# 05-USB-UART.net
KiCad netlist of a schematic drawn in Altium Designer
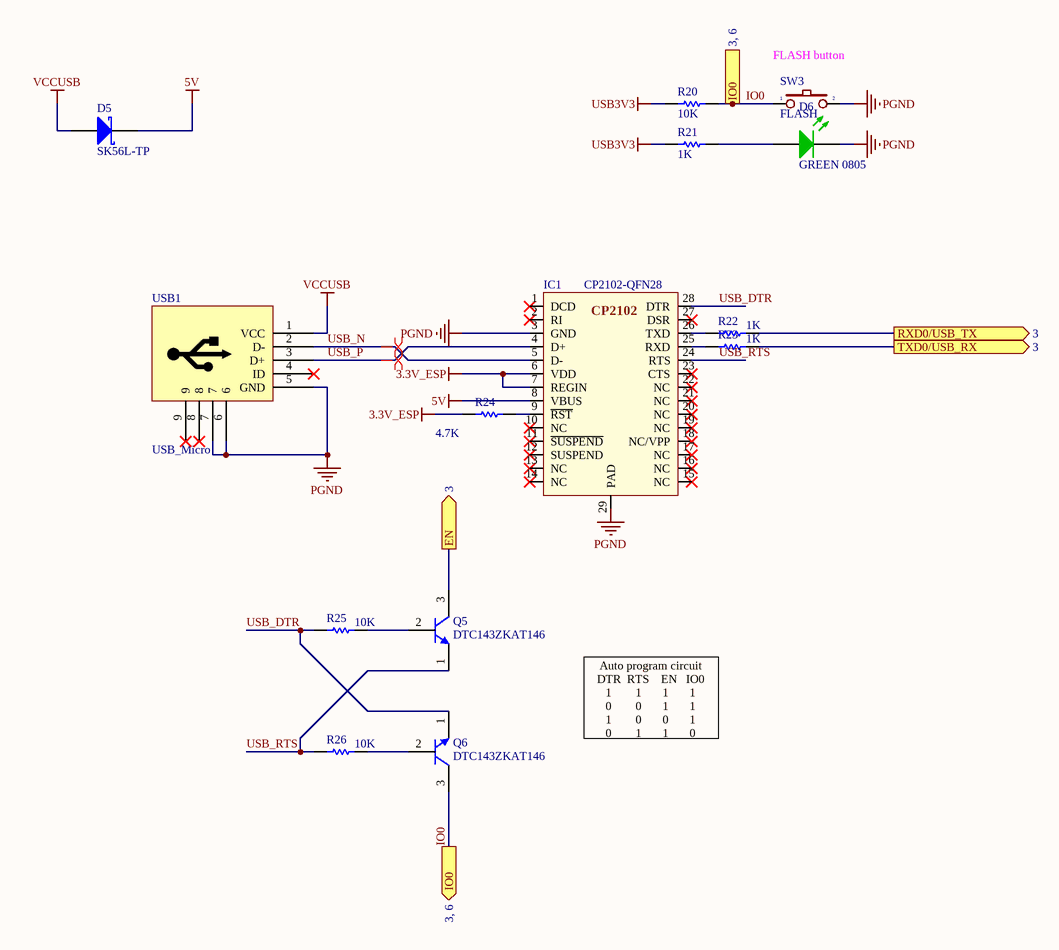
[diagram p0: 05-USB-UART.SchDoc]

(export (version "E")
  (design (tool "Eeschema 10.0.6"))
  (components
    (comp (ref "D5")
      (value "SK56L-TP")
      (footprint "30# SK56L-TPMSCT-ND")
      (description "DIODE SCHOTTKY 60V 5A DO214AB")
      (libsource (lib "GSHT_181013") (part "30# SK56L-TP"))
    )
    (comp (ref "D6")
      (value "GREEN 0805")
      (footprint "Led 0805G")
      (description "Green 571nm LED Indication - Discrete 2V 0805 (2012 Metric)")
      (libsource (lib "GSHT_181013") (part "LED GREEN 0603"))
    )
    (comp (ref "IC1")
      (value "CP2102-QFN28")
      (footprint "CP2102-QFN28")
      (description "USB Bridge, USB to UART USB 2.0 UART Interface 28-QFN (5x5)")
      (libsource (lib "lpson") (part "CP2102"))
    )
    (comp (ref "Q5")
      (value "DTC143ZKAT146")
      (footprint "6# DTC143ZKAT146-E")
      (description "Pre-Biased Bipolar Transistor (BJT) NPN - Pre-Biased 50V 100mA 250MHz 200mW Surface Mount SMT3")
      (libsource (lib "GSHT_181013") (part "6#DTC143ZKAT146"))
    )
    (comp (ref "Q6")
      (value "DTC143ZKAT146")
      (footprint "6# DTC143ZKAT146-E")
      (description "Pre-Biased Bipolar Transistor (BJT) NPN - Pre-Biased 50V 100mA 250MHz 200mW Surface Mount SMT3")
      (libsource (lib "GSHT_181013") (part "6#DTC143ZKAT146"))
    )
    (comp (ref "R20")
      (value "10K")
      (footprint "Res 0805 SMD")
      (description "10 kOhms ±1% 0.125W, 1/8W Chip Resistor 0805 (2012 Metric) Thick Film")
      (libsource (lib "GSHT_181013") (part "200K/R0603/1%"))
    )
    (comp (ref "R21")
      (value "1K")
      (footprint "Res 0805 SMD")
      (description "1 kOhms ±1% 0.125W, 1/8W Chip Resistor 0805 (2012 Metric) Automotive AEC-Q200 Thick Film")
      (libsource (lib "GSHT_181013") (part "200K/R0603/1%"))
    )
    (comp (ref "R22")
      (value "1K")
      (footprint "Res 0805 SMD")
      (description "1 kOhms ±1% 0.125W, 1/8W Chip Resistor 0805 (2012 Metric) Automotive AEC-Q200 Thick Film")
      (libsource (lib "GSHT_181013") (part "34.8K/R0805/1%"))
    )
    (comp (ref "R23")
      (value "1K")
      (footprint "Res 0805 SMD")
      (description "1 kOhms ±1% 0.125W, 1/8W Chip Resistor 0805 (2012 Metric) Automotive AEC-Q200 Thick Film")
      (libsource (lib "GSHT_181013") (part "34.8K/R0805/1%"))
    )
    (comp (ref "R24")
      (value "4.7K")
      (footprint "Res 0805 SMD")
      (description "4.7 kOhms ±1% 0.125W, 1/8W Chip Resistor 0805 (2012 Metric) Thick Film")
      (libsource (lib "GSHT_181013") (part "34.8K/R0805/1%"))
    )
    (comp (ref "R25")
      (value "10K")
      (footprint "Res 0805 SMD")
      (description "10 kOhms ±1% 0.125W, 1/8W Chip Resistor 0805 (2012 Metric) Thick Film")
      (libsource (lib "GSHT_181013") (part "34.8K/R0805/1%"))
    )
    (comp (ref "R26")
      (value "10K")
      (footprint "Res 0805 SMD")
      (description "10 kOhms ±1% 0.125W, 1/8W Chip Resistor 0805 (2012 Metric) Thick Film")
      (libsource (lib "GSHT_181013") (part "34.8K/R0805/1%"))
    )
    (comp (ref "SW3")
      (value "FLASH")
      (footprint "Button 3x4mm")
      (description "SWITCH TACTILE SPST-NO 0.05A 12V")
      (libsource (lib "lpson") (part "SW2"))
    )
    (comp (ref "USB1")
      (value "USB_Micro")
      (footprint "USB_MICRO_B - Digikey")
      (description "USB - micro B USB 2.0 Receptacle Connector 5 Position Surface Mount, Right Angle; Through Hole")
      (libsource (lib "lpson") (part "USB_MINI"))
    )
  )
  (nets
    (net (code "1") (name "/EN") (class "Default")
      (node (ref "Q5") (pin "3") (pinfunction "C_3") (pintype "passive"))
    )
    (net (code "2") (name "/IO0") (class "Default")
      (node (ref "Q6") (pin "3") (pinfunction "C_3") (pintype "passive"))
      (node (ref "R20") (pin "2") (pinfunction "2_2") (pintype "passive"))
      (node (ref "SW3") (pin "1") (pinfunction "1_1") (pintype "passive"))
    )
    (net (code "3") (name "/RXD0{slash}USB_TX") (class "Default")
      (node (ref "R22") (pin "1") (pinfunction "1_1") (pintype "passive"))
    )
    (net (code "4") (name "/TXD0{slash}USB_RX") (class "Default")
      (node (ref "R23") (pin "1") (pinfunction "1_1") (pintype "passive"))
    )
    (net (code "5") (name "/USB_DTR") (class "Default")
      (node (ref "IC1") (pin "28") (pinfunction "DTR_28") (pintype "passive"))
      (node (ref "Q6") (pin "1") (pinfunction "E_1") (pintype "passive"))
      (node (ref "R25") (pin "2") (pinfunction "2_2") (pintype "passive"))
    )
    (net (code "6") (name "/USB_N") (class "Default")
      (node (ref "IC1") (pin "5") (pinfunction "D-_5") (pintype "passive"))
      (node (ref "USB1") (pin "2") (pinfunction "D-_2") (pintype "passive"))
    )
    (net (code "7") (name "/USB_P") (class "Default")
      (node (ref "IC1") (pin "4") (pinfunction "D+_4") (pintype "passive"))
      (node (ref "USB1") (pin "3") (pinfunction "D+_3") (pintype "passive"))
    )
    (net (code "8") (name "/USB_RTS") (class "Default")
      (node (ref "IC1") (pin "24") (pinfunction "RTS_24") (pintype "passive"))
      (node (ref "Q5") (pin "1") (pinfunction "E_1") (pintype "passive"))
      (node (ref "R26") (pin "2") (pinfunction "2_2") (pintype "passive"))
    )
    (net (code "9") (name "3.3V_ESP") (class "Default")
      (node (ref "IC1") (pin "6") (pinfunction "VDD_6") (pintype "passive"))
      (node (ref "IC1") (pin "7") (pinfunction "REGIN_7") (pintype "passive"))
      (node (ref "R24") (pin "1") (pinfunction "1_1") (pintype "passive"))
    )
    (net (code "10") (name "5V") (class "Default")
      (node (ref "D5") (pin "2") (pinfunction "K_2") (pintype "passive"))
      (node (ref "IC1") (pin "8") (pinfunction "VBUS_8") (pintype "passive"))
    )
    (net (code "11") (name "Net-(D6-A)") (class "Default")
      (node (ref "D6") (pin "1") (pinfunction "A_1") (pintype "passive"))
      (node (ref "R21") (pin "2") (pinfunction "2_2") (pintype "passive"))
    )
    (net (code "12") (name "Net-(IC1-RXD)") (class "Default")
      (node (ref "IC1") (pin "25") (pinfunction "RXD_25") (pintype "passive"))
      (node (ref "R23") (pin "2") (pinfunction "2_2") (pintype "passive"))
    )
    (net (code "13") (name "Net-(IC1-TXD)") (class "Default")
      (node (ref "IC1") (pin "26") (pinfunction "TXD_26") (pintype "passive"))
      (node (ref "R22") (pin "2") (pinfunction "2_2") (pintype "passive"))
    )
    (net (code "14") (name "Net-(IC1-~{RST})") (class "Default")
      (node (ref "IC1") (pin "9") (pinfunction "~{RST}_9") (pintype "passive"))
      (node (ref "R24") (pin "2") (pinfunction "2_2") (pintype "passive"))
    )
    (net (code "15") (name "Net-(Q5-B)") (class "Default")
      (node (ref "Q5") (pin "2") (pinfunction "B_2") (pintype "passive"))
      (node (ref "R25") (pin "1") (pinfunction "1_1") (pintype "passive"))
    )
    (net (code "16") (name "Net-(Q6-B)") (class "Default")
      (node (ref "Q6") (pin "2") (pinfunction "B_2") (pintype "passive"))
      (node (ref "R26") (pin "1") (pinfunction "1_1") (pintype "passive"))
    )
    (net (code "17") (name "PGND") (class "Default")
      (node (ref "D6") (pin "2") (pinfunction "K_2") (pintype "passive"))
      (node (ref "IC1") (pin "29") (pinfunction "PAD_29") (pintype "passive"))
      (node (ref "IC1") (pin "3") (pinfunction "GND_3") (pintype "passive"))
      (node (ref "SW3") (pin "2") (pinfunction "2_2") (pintype "passive"))
      (node (ref "USB1") (pin "5") (pinfunction "GND_5") (pintype "passive"))
      (node (ref "USB1") (pin "6") (pinfunction "6_6") (pintype "passive"))
      (node (ref "USB1") (pin "7") (pinfunction "7_7") (pintype "passive"))
    )
    (net (code "18") (name "USB3V3") (class "Default")
      (node (ref "R20") (pin "1") (pinfunction "1_1") (pintype "passive"))
      (node (ref "R21") (pin "1") (pinfunction "1_1") (pintype "passive"))
    )
    (net (code "19") (name "VCCUSB") (class "Default")
      (node (ref "D5") (pin "1") (pinfunction "A_1") (pintype "passive"))
      (node (ref "USB1") (pin "1") (pinfunction "VCC_1") (pintype "passive"))
    )
    (net (code "20") (name "unconnected-(IC1-CTS-Pad23)") (class "Default")
      (node (ref "IC1") (pin "23") (pinfunction "CTS_23") (pintype "passive+no_connect"))
    )
    (net (code "21") (name "unconnected-(IC1-DCD-Pad1)") (class "Default")
      (node (ref "IC1") (pin "1") (pinfunction "DCD_1") (pintype "passive+no_connect"))
    )
    (net (code "22") (name "unconnected-(IC1-DSR-Pad27)") (class "Default")
      (node (ref "IC1") (pin "27") (pinfunction "DSR_27") (pintype "passive+no_connect"))
    )
    (net (code "23") (name "unconnected-(IC1-NC-Pad10)") (class "Default")
      (node (ref "IC1") (pin "10") (pinfunction "NC_10") (pintype "passive+no_connect"))
    )
    (net (code "24") (name "unconnected-(IC1-NC-Pad13)") (class "Default")
      (node (ref "IC1") (pin "13") (pinfunction "NC_13") (pintype "passive+no_connect"))
    )
    (net (code "25") (name "unconnected-(IC1-NC-Pad14)") (class "Default")
      (node (ref "IC1") (pin "14") (pinfunction "NC_14") (pintype "passive+no_connect"))
    )
    (net (code "26") (name "unconnected-(IC1-NC-Pad15)") (class "Default")
      (node (ref "IC1") (pin "15") (pinfunction "NC_15") (pintype "passive+no_connect"))
    )
    (net (code "27") (name "unconnected-(IC1-NC-Pad16)") (class "Default")
      (node (ref "IC1") (pin "16") (pinfunction "NC_16") (pintype "passive+no_connect"))
    )
    (net (code "28") (name "unconnected-(IC1-NC-Pad17)") (class "Default")
      (node (ref "IC1") (pin "17") (pinfunction "NC_17") (pintype "passive+no_connect"))
    )
    (net (code "29") (name "unconnected-(IC1-NC-Pad19)") (class "Default")
      (node (ref "IC1") (pin "19") (pinfunction "NC_19") (pintype "passive+no_connect"))
    )
    (net (code "30") (name "unconnected-(IC1-NC-Pad20)") (class "Default")
      (node (ref "IC1") (pin "20") (pinfunction "NC_20") (pintype "passive+no_connect"))
    )
    (net (code "31") (name "unconnected-(IC1-NC-Pad21)") (class "Default")
      (node (ref "IC1") (pin "21") (pinfunction "NC_21") (pintype "passive+no_connect"))
    )
    (net (code "32") (name "unconnected-(IC1-NC-Pad22)") (class "Default")
      (node (ref "IC1") (pin "22") (pinfunction "NC_22") (pintype "passive+no_connect"))
    )
    (net (code "33") (name "unconnected-(IC1-NC{slash}VPP-Pad18)") (class "Default")
      (node (ref "IC1") (pin "18") (pinfunction "NC/VPP_18") (pintype "passive+no_connect"))
    )
    (net (code "34") (name "unconnected-(IC1-RI-Pad2)") (class "Default")
      (node (ref "IC1") (pin "2") (pinfunction "RI_2") (pintype "passive+no_connect"))
    )
    (net (code "35") (name "unconnected-(IC1-SUSPEND-Pad12)") (class "Default")
      (node (ref "IC1") (pin "12") (pinfunction "SUSPEND_12") (pintype "passive+no_connect"))
    )
    (net (code "36") (name "unconnected-(IC1-~{SUSPEND}-Pad11)") (class "Default")
      (node (ref "IC1") (pin "11") (pinfunction "~{SUSPEND}_11") (pintype "passive+no_connect"))
    )
    (net (code "37") (name "unconnected-(USB1-ID-Pad4)") (class "Default")
      (node (ref "USB1") (pin "4") (pinfunction "ID_4") (pintype "passive+no_connect"))
    )
    (net (code "38") (name "unconnected-(USB1-Pad8)") (class "Default")
      (node (ref "USB1") (pin "8") (pinfunction "8_8") (pintype "passive+no_connect"))
    )
    (net (code "39") (name "unconnected-(USB1-Pad9)") (class "Default")
      (node (ref "USB1") (pin "9") (pinfunction "9_9") (pintype "passive+no_connect"))
    )
  )
)
